# Sensing_-_Temperature.net
KiCad netlist of a schematic drawn in Altium Designer
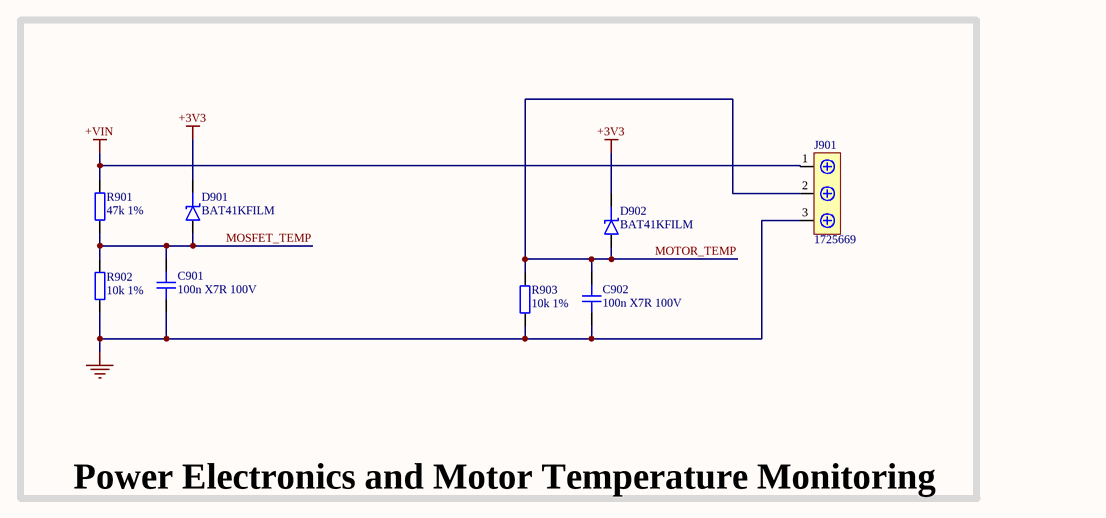
[diagram p0: Sensing - Temperature.SchDoc]

(export (version "E")
  (design (tool "Eeschema 10.0.6"))
  (components
    (comp (ref "C901")
      (value "100n X7R 100V")
      (footprint "CAP_0603")
      (description "Capacitor SMD 0603")
      (fields
        (field (name "MANUFACTURER") "CCTC")
        (field (name "MANUFACTURER PART NUMBER") "TCC0603X7R104K101CT")
      )
      (libsource (lib "Schematic-Lib-PhilsLab") (part "CAP_0603"))
    )
    (comp (ref "C902")
      (value "100n X7R 100V")
      (footprint "CAP_0603")
      (description "Capacitor SMD 0603")
      (fields
        (field (name "MANUFACTURER") "CCTC")
        (field (name "MANUFACTURER PART NUMBER") "TCC0603X7R104K101CT")
      )
      (libsource (lib "Schematic-Lib-PhilsLab") (part "CAP_0603"))
    )
    (comp (ref "D901")
      (value "BAT41KFILM")
      (footprint "SOD-523")
      (description "Diode Schottky SMD SOD-323")
      (fields (field (name "MANUFACTURER") "STMicroelectronics"))
      (libsource (lib "Schematic-Lib-PhilsLab") (part "D_SCHOTTKY_SOD_523"))
    )
    (comp (ref "D902")
      (value "BAT41KFILM")
      (footprint "SOD-523")
      (description "Diode Schottky SMD SOD-323")
      (fields (field (name "MANUFACTURER") "STMicroelectronics"))
      (libsource (lib "Schematic-Lib-PhilsLab") (part "D_SCHOTTKY_SOD_523"))
    )
    (comp (ref "J901")
      (value "1725669")
      (footprint "1725669")
      (description "Screw Terminal Block 3 Positions 2.54mm")
      (fields (field (name "MANUFACTURER") "Phoenix"))
      (libsource (lib "Schematic-Lib") (part "1725669"))
    )
    (comp (ref "R901")
      (value "47k 1%")
      (footprint "RES_0603")
      (description "Resistor SMD 0603")
      (fields
        (field (name "MANUFACTURER") "Vishay Intertech")
        (field (name "MANUFACTURER PART NUMBER") "NTCS0603E3473FHT")
      )
      (libsource (lib "Schematic-Lib-PhilsLab") (part "RES_0603"))
    )
    (comp (ref "R902")
      (value "10k 1%")
      (footprint "RES_0603")
      (description "Resistor SMD 0603")
      (fields
        (field (name "MANUFACTURER") "YAGEO")
        (field (name "MANUFACTURER PART NUMBER") "RC0603FR-07140KL")
      )
      (libsource (lib "Schematic-Lib-PhilsLab") (part "RES_0603"))
    )
    (comp (ref "R903")
      (value "10k 1%")
      (footprint "RES_0603")
      (description "Resistor SMD 0603")
      (fields
        (field (name "MANUFACTURER") "YAGEO")
        (field (name "MANUFACTURER PART NUMBER") "RC0603FR-07140KL")
      )
      (libsource (lib "Schematic-Lib-PhilsLab") (part "RES_0603"))
    )
  )
  (nets
    (net (code "1") (name "+3V3") (class "Default")
      (node (ref "D901") (pin "K") (pinfunction "K_K") (pintype "passive"))
      (node (ref "D902") (pin "K") (pinfunction "K_K") (pintype "passive"))
    )
    (net (code "2") (name "+VIN") (class "Default")
      (node (ref "J901") (pin "1") (pinfunction "1_1") (pintype "passive"))
      (node (ref "R901") (pin "2") (pinfunction "2_2") (pintype "passive"))
    )
    (net (code "3") (name "/MOSFET_TEMP") (class "Default")
      (node (ref "C901") (pin "2") (pinfunction "2_2") (pintype "passive"))
      (node (ref "D901") (pin "A") (pinfunction "A_A") (pintype "passive"))
      (node (ref "R901") (pin "1") (pinfunction "1_1") (pintype "passive"))
      (node (ref "R902") (pin "2") (pinfunction "2_2") (pintype "passive"))
    )
    (net (code "4") (name "/MOTOR_TEMP") (class "Default")
      (node (ref "C902") (pin "2") (pinfunction "2_2") (pintype "passive"))
      (node (ref "D902") (pin "A") (pinfunction "A_A") (pintype "passive"))
      (node (ref "J901") (pin "2") (pinfunction "2_2") (pintype "passive"))
      (node (ref "R903") (pin "2") (pinfunction "2_2") (pintype "passive"))
    )
    (net (code "5") (name "GND") (class "Default")
      (node (ref "C901") (pin "1") (pinfunction "1_1") (pintype "passive"))
      (node (ref "C902") (pin "1") (pinfunction "1_1") (pintype "passive"))
      (node (ref "J901") (pin "3") (pinfunction "3_3") (pintype "passive"))
      (node (ref "R902") (pin "1") (pinfunction "1_1") (pintype "passive"))
      (node (ref "R903") (pin "1") (pinfunction "1_1") (pintype "passive"))
    )
  )
)
